# main.net
KiCad netlist of a schematic drawn in Altium Designer
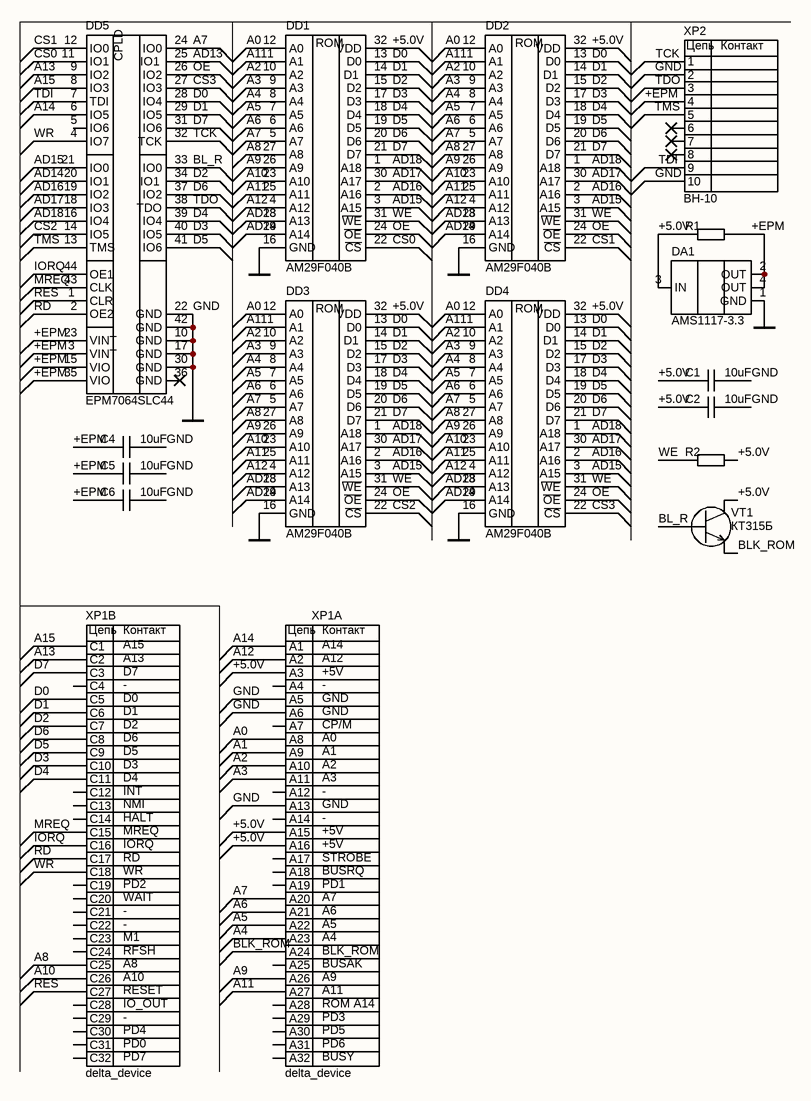
[diagram p0: main.SchDoc]

(export (version "E")
  (design (tool "Eeschema 10.0.6"))
  (components
    (comp (ref "C1") (value "10uF") (footprint "C0805") (libsource (lib "Capacitors") (part "CapCer")))
    (comp (ref "C2") (value "10uF") (footprint "C0805") (libsource (lib "Capacitors") (part "CapCer")))
    (comp (ref "C4") (value "10uF") (footprint "C0805") (libsource (lib "Capacitors") (part "CapCer")))
    (comp (ref "C5") (value "10uF") (footprint "C0805") (libsource (lib "Capacitors") (part "CapCer")))
    (comp (ref "C6") (value "10uF") (footprint "C0805") (libsource (lib "Capacitors") (part "CapCer")))
    (comp (ref "DA1")
      (value "AMS1117-3.3")
      (footprint "SOT229P700X180-4N")
      (libsource (lib "LDO") (part "AMS1117-3.3"))
    )
    (comp (ref "DD1")
      (value "AM29F040B")
      (footprint "DIP254P1524X482-32")
      (libsource (lib "ROM") (part "AM29F040B"))
    )
    (comp (ref "DD2")
      (value "AM29F040B")
      (footprint "DIP254P1524X482-32")
      (libsource (lib "ROM") (part "AM29F040B"))
    )
    (comp (ref "DD3")
      (value "AM29F040B")
      (footprint "DIP254P1524X482-32")
      (libsource (lib "ROM") (part "AM29F040B"))
    )
    (comp (ref "DD4")
      (value "AM29F040B")
      (footprint "DIP254P1524X482-32")
      (libsource (lib "ROM") (part "AM29F040B"))
    )
    (comp (ref "DD5")
      (value "EPM7064SLC44")
      (footprint "PLCC-44-R")
      (description "44-Pin PLCC44")
      (libsource (lib "cpld") (part "EPM7064SLC44"))
    )
    (comp (ref "R1") (value "0 Ом") (footprint "R0603") (libsource (lib "Resistors") (part "Res")))
    (comp (ref "R2") (value "1 кОм") (footprint "R0603") (libsource (lib "Resistors") (part "Res")))
    (comp (ref "VT1")
      (value "КТ315Б")
      (footprint "KT-13")
      (description "NPN Transistor")
      (libsource (lib "Transistors") (part "КТ315Б"))
    )
    (comp (ref "XP1")
      (value "delta_device")
      (footprint "delta-device")
      (libsource (lib "Connectors") (part "delta_device"))
    )
    (comp (ref "XP2")
      (value "BH-10")
      (footprint "BH-10")
      (description "10 Position Total Dual Row 2.54 mm Pitch Straight Male Shrouded Box Header")
      (fields (field (name "MF") "Sullins Connector") (field (name "MP") "SBH11-PBPC-D05-ST-BK"))
      (libsource (lib "Connectors") (part "BH-10"))
    )
  )
  (nets
    (net (code "1") (name "/+5.0V") (class "Default")
      (node (ref "C1") (pin "1") (pinfunction "1_1") (pintype "passive"))
      (node (ref "C2") (pin "1") (pinfunction "1_1") (pintype "passive"))
      (node (ref "DA1") (pin "3") (pinfunction "IN_3") (pintype "passive"))
      (node (ref "DD1") (pin "32") (pinfunction "VDD_32") (pintype "passive"))
      (node (ref "DD2") (pin "32") (pinfunction "VDD_32") (pintype "passive"))
      (node (ref "DD3") (pin "32") (pinfunction "VDD_32") (pintype "passive"))
      (node (ref "DD4") (pin "32") (pinfunction "VDD_32") (pintype "passive"))
      (node (ref "R1") (pin "1") (pinfunction "1_1") (pintype "passive"))
      (node (ref "R2") (pin "2") (pinfunction "2_2") (pintype "passive"))
      (node (ref "VT1") (pin "2") (pinfunction "C_2") (pintype "power_in"))
      (node (ref "XP1") (pin "A15") (pinfunction "A15_A15") (pintype "passive"))
      (node (ref "XP1") (pin "A16") (pinfunction "A16_A16") (pintype "passive"))
      (node (ref "XP1") (pin "A3") (pinfunction "A3_A3") (pintype "passive"))
    )
    (net (code "2") (name "/+EPM") (class "Default")
      (node (ref "C4") (pin "1") (pinfunction "1_1") (pintype "passive"))
      (node (ref "C5") (pin "1") (pinfunction "1_1") (pintype "passive"))
      (node (ref "C6") (pin "1") (pinfunction "1_1") (pintype "passive"))
      (node (ref "DA1") (pin "2") (pinfunction "OUT_2") (pintype "passive"))
      (node (ref "DA1") (pin "4") (pinfunction "OUT_4") (pintype "passive"))
      (node (ref "DD5") (pin "15") (pinfunction "VIO_15") (pintype "passive"))
      (node (ref "DD5") (pin "23") (pinfunction "VINT_23") (pintype "passive"))
      (node (ref "DD5") (pin "3") (pinfunction "VINT_3") (pintype "passive"))
      (node (ref "DD5") (pin "35") (pinfunction "VIO_35") (pintype "passive"))
      (node (ref "R1") (pin "2") (pinfunction "2_2") (pintype "passive"))
      (node (ref "XP2") (pin "4") (pinfunction "4_4") (pintype "passive"))
    )
    (net (code "3") (name "/A0") (class "Default")
      (node (ref "DD1") (pin "12") (pinfunction "A0_12") (pintype "passive"))
      (node (ref "DD2") (pin "12") (pinfunction "A0_12") (pintype "passive"))
      (node (ref "DD3") (pin "12") (pinfunction "A0_12") (pintype "passive"))
      (node (ref "DD4") (pin "12") (pinfunction "A0_12") (pintype "passive"))
      (node (ref "XP1") (pin "A8") (pinfunction "A8_A8") (pintype "passive"))
    )
    (net (code "4") (name "/A1") (class "Default")
      (node (ref "DD1") (pin "11") (pinfunction "A1_11") (pintype "passive"))
      (node (ref "DD2") (pin "11") (pinfunction "A1_11") (pintype "passive"))
      (node (ref "DD3") (pin "11") (pinfunction "A1_11") (pintype "passive"))
      (node (ref "DD4") (pin "11") (pinfunction "A1_11") (pintype "passive"))
      (node (ref "XP1") (pin "A9") (pinfunction "A9_A9") (pintype "passive"))
    )
    (net (code "5") (name "/A2") (class "Default")
      (node (ref "DD1") (pin "10") (pinfunction "A2_10") (pintype "passive"))
      (node (ref "DD2") (pin "10") (pinfunction "A2_10") (pintype "passive"))
      (node (ref "DD3") (pin "10") (pinfunction "A2_10") (pintype "passive"))
      (node (ref "DD4") (pin "10") (pinfunction "A2_10") (pintype "passive"))
      (node (ref "XP1") (pin "A10") (pinfunction "A10_A10") (pintype "passive"))
    )
    (net (code "6") (name "/A3") (class "Default")
      (node (ref "DD1") (pin "9") (pinfunction "A3_9") (pintype "passive"))
      (node (ref "DD2") (pin "9") (pinfunction "A3_9") (pintype "passive"))
      (node (ref "DD3") (pin "9") (pinfunction "A3_9") (pintype "passive"))
      (node (ref "DD4") (pin "9") (pinfunction "A3_9") (pintype "passive"))
      (node (ref "XP1") (pin "A11") (pinfunction "A11_A11") (pintype "passive"))
    )
    (net (code "7") (name "/A4") (class "Default")
      (node (ref "DD1") (pin "8") (pinfunction "A4_8") (pintype "passive"))
      (node (ref "DD2") (pin "8") (pinfunction "A4_8") (pintype "passive"))
      (node (ref "DD3") (pin "8") (pinfunction "A4_8") (pintype "passive"))
      (node (ref "DD4") (pin "8") (pinfunction "A4_8") (pintype "passive"))
      (node (ref "XP1") (pin "A23") (pinfunction "A23_A23") (pintype "passive"))
    )
    (net (code "8") (name "/A5") (class "Default")
      (node (ref "DD1") (pin "7") (pinfunction "A5_7") (pintype "passive"))
      (node (ref "DD2") (pin "7") (pinfunction "A5_7") (pintype "passive"))
      (node (ref "DD3") (pin "7") (pinfunction "A5_7") (pintype "passive"))
      (node (ref "DD4") (pin "7") (pinfunction "A5_7") (pintype "passive"))
      (node (ref "XP1") (pin "A22") (pinfunction "A22_A22") (pintype "passive"))
    )
    (net (code "9") (name "/A6") (class "Default")
      (node (ref "DD1") (pin "6") (pinfunction "A6_6") (pintype "passive"))
      (node (ref "DD2") (pin "6") (pinfunction "A6_6") (pintype "passive"))
      (node (ref "DD3") (pin "6") (pinfunction "A6_6") (pintype "passive"))
      (node (ref "DD4") (pin "6") (pinfunction "A6_6") (pintype "passive"))
      (node (ref "XP1") (pin "A21") (pinfunction "A21_A21") (pintype "passive"))
    )
    (net (code "10") (name "/A7") (class "Default")
      (node (ref "DD1") (pin "5") (pinfunction "A7_5") (pintype "passive"))
      (node (ref "DD2") (pin "5") (pinfunction "A7_5") (pintype "passive"))
      (node (ref "DD3") (pin "5") (pinfunction "A7_5") (pintype "passive"))
      (node (ref "DD4") (pin "5") (pinfunction "A7_5") (pintype "passive"))
      (node (ref "DD5") (pin "24") (pinfunction "IO0_24") (pintype "passive"))
      (node (ref "XP1") (pin "A20") (pinfunction "A20_A20") (pintype "passive"))
    )
    (net (code "11") (name "/A8") (class "Default")
      (node (ref "DD1") (pin "27") (pinfunction "A8_27") (pintype "passive"))
      (node (ref "DD2") (pin "27") (pinfunction "A8_27") (pintype "passive"))
      (node (ref "DD3") (pin "27") (pinfunction "A8_27") (pintype "passive"))
      (node (ref "DD4") (pin "27") (pinfunction "A8_27") (pintype "passive"))
      (node (ref "XP1") (pin "C25") (pinfunction "C25_C25") (pintype "passive"))
    )
    (net (code "12") (name "/A9") (class "Default")
      (node (ref "DD1") (pin "26") (pinfunction "A9_26") (pintype "passive"))
      (node (ref "DD2") (pin "26") (pinfunction "A9_26") (pintype "passive"))
      (node (ref "DD3") (pin "26") (pinfunction "A9_26") (pintype "passive"))
      (node (ref "DD4") (pin "26") (pinfunction "A9_26") (pintype "passive"))
      (node (ref "XP1") (pin "A26") (pinfunction "A26_A26") (pintype "passive"))
    )
    (net (code "13") (name "/A10") (class "Default")
      (node (ref "DD1") (pin "23") (pinfunction "A10_23") (pintype "passive"))
      (node (ref "DD2") (pin "23") (pinfunction "A10_23") (pintype "passive"))
      (node (ref "DD3") (pin "23") (pinfunction "A10_23") (pintype "passive"))
      (node (ref "DD4") (pin "23") (pinfunction "A10_23") (pintype "passive"))
      (node (ref "XP1") (pin "C26") (pinfunction "C26_C26") (pintype "passive"))
    )
    (net (code "14") (name "/A11") (class "Default")
      (node (ref "DD1") (pin "25") (pinfunction "A11_25") (pintype "passive"))
      (node (ref "DD2") (pin "25") (pinfunction "A11_25") (pintype "passive"))
      (node (ref "DD3") (pin "25") (pinfunction "A11_25") (pintype "passive"))
      (node (ref "DD4") (pin "25") (pinfunction "A11_25") (pintype "passive"))
      (node (ref "XP1") (pin "A27") (pinfunction "A27_A27") (pintype "passive"))
    )
    (net (code "15") (name "/A12") (class "Default")
      (node (ref "DD1") (pin "4") (pinfunction "A12_4") (pintype "passive"))
      (node (ref "DD2") (pin "4") (pinfunction "A12_4") (pintype "passive"))
      (node (ref "DD3") (pin "4") (pinfunction "A12_4") (pintype "passive"))
      (node (ref "DD4") (pin "4") (pinfunction "A12_4") (pintype "passive"))
      (node (ref "XP1") (pin "A2") (pinfunction "A2_A2") (pintype "passive"))
    )
    (net (code "16") (name "/A13") (class "Default")
      (node (ref "DD5") (pin "9") (pinfunction "IO2_9") (pintype "passive"))
      (node (ref "XP1") (pin "C2") (pinfunction "C2_C2") (pintype "passive"))
    )
    (net (code "17") (name "/A14") (class "Default")
      (node (ref "DD5") (pin "6") (pinfunction "IO5_6") (pintype "passive"))
      (node (ref "XP1") (pin "A1") (pinfunction "A1_A1") (pintype "passive"))
    )
    (net (code "18") (name "/A15") (class "Default")
      (node (ref "DD5") (pin "8") (pinfunction "IO3_8") (pintype "passive"))
      (node (ref "XP1") (pin "C1") (pinfunction "C1_C1") (pintype "passive"))
    )
    (net (code "19") (name "/AD13") (class "Default")
      (node (ref "DD1") (pin "28") (pinfunction "A13_28") (pintype "passive"))
      (node (ref "DD2") (pin "28") (pinfunction "A13_28") (pintype "passive"))
      (node (ref "DD3") (pin "28") (pinfunction "A13_28") (pintype "passive"))
      (node (ref "DD4") (pin "28") (pinfunction "A13_28") (pintype "passive"))
      (node (ref "DD5") (pin "25") (pinfunction "IO1_25") (pintype "passive"))
    )
    (net (code "20") (name "/AD14") (class "Default")
      (node (ref "DD1") (pin "29") (pinfunction "A14_29") (pintype "passive"))
      (node (ref "DD2") (pin "29") (pinfunction "A14_29") (pintype "passive"))
      (node (ref "DD3") (pin "29") (pinfunction "A14_29") (pintype "passive"))
      (node (ref "DD4") (pin "29") (pinfunction "A14_29") (pintype "passive"))
      (node (ref "DD5") (pin "20") (pinfunction "IO1_20") (pintype "passive"))
    )
    (net (code "21") (name "/AD15") (class "Default")
      (node (ref "DD1") (pin "3") (pinfunction "A15_3") (pintype "passive"))
      (node (ref "DD2") (pin "3") (pinfunction "A15_3") (pintype "passive"))
      (node (ref "DD3") (pin "3") (pinfunction "A15_3") (pintype "passive"))
      (node (ref "DD4") (pin "3") (pinfunction "A15_3") (pintype "passive"))
      (node (ref "DD5") (pin "21") (pinfunction "IO0_21") (pintype "passive"))
    )
    (net (code "22") (name "/AD16") (class "Default")
      (node (ref "DD1") (pin "2") (pinfunction "A16_2") (pintype "passive"))
      (node (ref "DD2") (pin "2") (pinfunction "A16_2") (pintype "passive"))
      (node (ref "DD3") (pin "2") (pinfunction "A16_2") (pintype "passive"))
      (node (ref "DD4") (pin "2") (pinfunction "A16_2") (pintype "passive"))
      (node (ref "DD5") (pin "19") (pinfunction "IO2_19") (pintype "passive"))
    )
    (net (code "23") (name "/AD17") (class "Default")
      (node (ref "DD1") (pin "30") (pinfunction "A17_30") (pintype "passive"))
      (node (ref "DD2") (pin "30") (pinfunction "A17_30") (pintype "passive"))
      (node (ref "DD3") (pin "30") (pinfunction "A17_30") (pintype "passive"))
      (node (ref "DD4") (pin "30") (pinfunction "A17_30") (pintype "passive"))
      (node (ref "DD5") (pin "18") (pinfunction "IO3_18") (pintype "passive"))
    )
    (net (code "24") (name "/AD18") (class "Default")
      (node (ref "DD1") (pin "1") (pinfunction "A18_1") (pintype "passive"))
      (node (ref "DD2") (pin "1") (pinfunction "A18_1") (pintype "passive"))
      (node (ref "DD3") (pin "1") (pinfunction "A18_1") (pintype "passive"))
      (node (ref "DD4") (pin "1") (pinfunction "A18_1") (pintype "passive"))
      (node (ref "DD5") (pin "16") (pinfunction "IO4_16") (pintype "passive"))
    )
    (net (code "25") (name "/BLK_ROM") (class "Default")
      (node (ref "VT1") (pin "1") (pinfunction "E_1") (pintype "power_in"))
      (node (ref "XP1") (pin "A24") (pinfunction "A24_A24") (pintype "passive"))
    )
    (net (code "26") (name "/BL_R") (class "Default")
      (node (ref "DD5") (pin "33") (pinfunction "IO0_33") (pintype "passive"))
      (node (ref "VT1") (pin "3") (pinfunction "B_3") (pintype "power_in"))
    )
    (net (code "27") (name "/CS0") (class "Default")
      (node (ref "DD1") (pin "22") (pinfunction "~{CS}_22") (pintype "passive"))
      (node (ref "DD5") (pin "11") (pinfunction "IO1_11") (pintype "passive"))
    )
    (net (code "28") (name "/CS1") (class "Default")
      (node (ref "DD2") (pin "22") (pinfunction "~{CS}_22") (pintype "passive"))
      (node (ref "DD5") (pin "12") (pinfunction "IO0_12") (pintype "passive"))
    )
    (net (code "29") (name "/CS2") (class "Default")
      (node (ref "DD3") (pin "22") (pinfunction "~{CS}_22") (pintype "passive"))
      (node (ref "DD5") (pin "14") (pinfunction "IO5_14") (pintype "passive"))
    )
    (net (code "30") (name "/CS3") (class "Default")
      (node (ref "DD4") (pin "22") (pinfunction "~{CS}_22") (pintype "passive"))
      (node (ref "DD5") (pin "27") (pinfunction "IO3_27") (pintype "passive"))
    )
    (net (code "31") (name "/D0") (class "Default")
      (node (ref "DD1") (pin "13") (pinfunction "D0_13") (pintype "passive"))
      (node (ref "DD2") (pin "13") (pinfunction "D0_13") (pintype "passive"))
      (node (ref "DD3") (pin "13") (pinfunction "D0_13") (pintype "passive"))
      (node (ref "DD4") (pin "13") (pinfunction "D0_13") (pintype "passive"))
      (node (ref "DD5") (pin "28") (pinfunction "IO4_28") (pintype "passive"))
      (node (ref "XP1") (pin "C5") (pinfunction "C5_C5") (pintype "passive"))
    )
    (net (code "32") (name "/D1") (class "Default")
      (node (ref "DD1") (pin "14") (pinfunction "D1_14") (pintype "passive"))
      (node (ref "DD2") (pin "14") (pinfunction "D1_14") (pintype "passive"))
      (node (ref "DD3") (pin "14") (pinfunction "D1_14") (pintype "passive"))
      (node (ref "DD4") (pin "14") (pinfunction "D1_14") (pintype "passive"))
      (node (ref "DD5") (pin "29") (pinfunction "IO5_29") (pintype "passive"))
      (node (ref "XP1") (pin "C6") (pinfunction "C6_C6") (pintype "passive"))
    )
    (net (code "33") (name "/D2") (class "Default")
      (node (ref "DD1") (pin "15") (pinfunction "D2_15") (pintype "passive"))
      (node (ref "DD2") (pin "15") (pinfunction "D2_15") (pintype "passive"))
      (node (ref "DD3") (pin "15") (pinfunction "D2_15") (pintype "passive"))
      (node (ref "DD4") (pin "15") (pinfunction "D2_15") (pintype "passive"))
      (node (ref "DD5") (pin "34") (pinfunction "IO1_34") (pintype "passive"))
      (node (ref "XP1") (pin "C7") (pinfunction "C7_C7") (pintype "passive"))
    )
    (net (code "34") (name "/D3") (class "Default")
      (node (ref "DD1") (pin "17") (pinfunction "D3_17") (pintype "passive"))
      (node (ref "DD2") (pin "17") (pinfunction "D3_17") (pintype "passive"))
      (node (ref "DD3") (pin "17") (pinfunction "D3_17") (pintype "passive"))
      (node (ref "DD4") (pin "17") (pinfunction "D3_17") (pintype "passive"))
      (node (ref "DD5") (pin "40") (pinfunction "IO5_40") (pintype "passive"))
      (node (ref "XP1") (pin "C10") (pinfunction "C10_C10") (pintype "passive"))
    )
    (net (code "35") (name "/D4") (class "Default")
      (node (ref "DD1") (pin "18") (pinfunction "D4_18") (pintype "passive"))
      (node (ref "DD2") (pin "18") (pinfunction "D4_18") (pintype "passive"))
      (node (ref "DD3") (pin "18") (pinfunction "D4_18") (pintype "passive"))
      (node (ref "DD4") (pin "18") (pinfunction "D4_18") (pintype "passive"))
      (node (ref "DD5") (pin "39") (pinfunction "IO4_39") (pintype "passive"))
      (node (ref "XP1") (pin "C11") (pinfunction "C11_C11") (pintype "passive"))
    )
    (net (code "36") (name "/D5") (class "Default")
      (node (ref "DD1") (pin "19") (pinfunction "D5_19") (pintype "passive"))
      (node (ref "DD2") (pin "19") (pinfunction "D5_19") (pintype "passive"))
      (node (ref "DD3") (pin "19") (pinfunction "D5_19") (pintype "passive"))
      (node (ref "DD4") (pin "19") (pinfunction "D5_19") (pintype "passive"))
      (node (ref "DD5") (pin "41") (pinfunction "IO6_41") (pintype "passive"))
      (node (ref "XP1") (pin "C9") (pinfunction "C9_C9") (pintype "passive"))
    )
    (net (code "37") (name "/D6") (class "Default")
      (node (ref "DD1") (pin "20") (pinfunction "D6_20") (pintype "passive"))
      (node (ref "DD2") (pin "20") (pinfunction "D6_20") (pintype "passive"))
      (node (ref "DD3") (pin "20") (pinfunction "D6_20") (pintype "passive"))
      (node (ref "DD4") (pin "20") (pinfunction "D6_20") (pintype "passive"))
      (node (ref "DD5") (pin "37") (pinfunction "IO2_37") (pintype "passive"))
      (node (ref "XP1") (pin "C8") (pinfunction "C8_C8") (pintype "passive"))
    )
    (net (code "38") (name "/D7") (class "Default")
      (node (ref "DD1") (pin "21") (pinfunction "D7_21") (pintype "passive"))
      (node (ref "DD2") (pin "21") (pinfunction "D7_21") (pintype "passive"))
      (node (ref "DD3") (pin "21") (pinfunction "D7_21") (pintype "passive"))
      (node (ref "DD4") (pin "21") (pinfunction "D7_21") (pintype "passive"))
      (node (ref "DD5") (pin "31") (pinfunction "IO6_31") (pintype "passive"))
      (node (ref "XP1") (pin "C3") (pinfunction "C3_C3") (pintype "passive"))
    )
    (net (code "39") (name "/IORQ") (class "Default")
      (node (ref "DD5") (pin "44") (pinfunction "OE1_44") (pintype "passive"))
      (node (ref "XP1") (pin "C16") (pinfunction "C16_C16") (pintype "passive"))
    )
    (net (code "40") (name "/MREQ") (class "Default")
      (node (ref "DD5") (pin "43") (pinfunction "CLK_43") (pintype "passive"))
      (node (ref "XP1") (pin "C15") (pinfunction "C15_C15") (pintype "passive"))
    )
    (net (code "41") (name "/OE") (class "Default")
      (node (ref "DD1") (pin "24") (pinfunction "~{OE}_24") (pintype "passive"))
      (node (ref "DD2") (pin "24") (pinfunction "~{OE}_24") (pintype "passive"))
      (node (ref "DD3") (pin "24") (pinfunction "~{OE}_24") (pintype "passive"))
      (node (ref "DD4") (pin "24") (pinfunction "~{OE}_24") (pintype "passive"))
      (node (ref "DD5") (pin "26") (pinfunction "IO2_26") (pintype "passive"))
    )
    (net (code "42") (name "/RD") (class "Default")
      (node (ref "DD5") (pin "2") (pinfunction "OE2_2") (pintype "passive"))
      (node (ref "XP1") (pin "C17") (pinfunction "C17_C17") (pintype "passive"))
    )
    (net (code "43") (name "/RES") (class "Default")
      (node (ref "DD5") (pin "1") (pinfunction "CLR_1") (pintype "passive"))
      (node (ref "XP1") (pin "C27") (pinfunction "C27_C27") (pintype "passive"))
    )
    (net (code "44") (name "/TCK") (class "Default")
      (node (ref "DD5") (pin "32") (pinfunction "TCK_32") (pintype "passive"))
      (node (ref "XP2") (pin "1") (pinfunction "1_1") (pintype "passive"))
    )
    (net (code "45") (name "/TDI") (class "Default")
      (node (ref "DD5") (pin "7") (pinfunction "TDI_7") (pintype "passive"))
      (node (ref "XP2") (pin "9") (pinfunction "9_9") (pintype "passive"))
    )
    (net (code "46") (name "/TDO") (class "Default")
      (node (ref "DD5") (pin "38") (pinfunction "TDO_38") (pintype "passive"))
      (node (ref "XP2") (pin "3") (pinfunction "3_3") (pintype "passive"))
    )
    (net (code "47") (name "/TMS") (class "Default")
      (node (ref "DD5") (pin "13") (pinfunction "TMS_13") (pintype "passive"))
      (node (ref "XP2") (pin "5") (pinfunction "5_5") (pintype "passive"))
    )
    (net (code "48") (name "/WE") (class "Default")
      (node (ref "DD1") (pin "31") (pinfunction "~{WE}_31") (pintype "passive"))
      (node (ref "DD2") (pin "31") (pinfunction "~{WE}_31") (pintype "passive"))
      (node (ref "DD3") (pin "31") (pinfunction "~{WE}_31") (pintype "passive"))
      (node (ref "DD4") (pin "31") (pinfunction "~{WE}_31") (pintype "passive"))
      (node (ref "R2") (pin "1") (pinfunction "1_1") (pintype "passive"))
    )
    (net (code "49") (name "/WR") (class "Default")
      (node (ref "DD5") (pin "4") (pinfunction "IO7_4") (pintype "passive"))
      (node (ref "XP1") (pin "C18") (pinfunction "C18_C18") (pintype "passive"))
    )
    (net (code "50") (name "GND") (class "Default")
      (node (ref "C1") (pin "2") (pinfunction "2_2") (pintype "passive"))
      (node (ref "C2") (pin "2") (pinfunction "2_2") (pintype "passive"))
      (node (ref "C4") (pin "2") (pinfunction "2_2") (pintype "passive"))
      (node (ref "C5") (pin "2") (pinfunction "2_2") (pintype "passive"))
      (node (ref "C6") (pin "2") (pinfunction "2_2") (pintype "passive"))
      (node (ref "DA1") (pin "1") (pinfunction "GND_1") (pintype "passive"))
      (node (ref "DD1") (pin "16") (pinfunction "GND_16") (pintype "passive"))
      (node (ref "DD2") (pin "16") (pinfunction "GND_16") (pintype "passive"))
      (node (ref "DD3") (pin "16") (pinfunction "GND_16") (pintype "passive"))
      (node (ref "DD4") (pin "16") (pinfunction "GND_16") (pintype "passive"))
      (node (ref "DD5") (pin "10") (pinfunction "GND_10") (pintype "passive"))
      (node (ref "DD5") (pin "17") (pinfunction "GND_17") (pintype "passive"))
      (node (ref "DD5") (pin "22") (pinfunction "GND_22") (pintype "passive"))
      (node (ref "DD5") (pin "30") (pinfunction "GND_30") (pintype "passive"))
      (node (ref "DD5") (pin "42") (pinfunction "GND_42") (pintype "passive"))
      (node (ref "XP1") (pin "A13") (pinfunction "A13_A13") (pintype "passive"))
      (node (ref "XP1") (pin "A5") (pinfunction "A5_A5") (pintype "passive"))
      (node (ref "XP1") (pin "A6") (pinfunction "A6_A6") (pintype "passive"))
      (node (ref "XP2") (pin "10") (pinfunction "10_10") (pintype "passive"))
      (node (ref "XP2") (pin "2") (pinfunction "2_2") (pintype "passive"))
    )
    (net (code "51") (name "unconnected-(DD5-GND-Pad36)") (class "Default")
      (node (ref "DD5") (pin "36") (pinfunction "GND_36") (pintype "passive+no_connect"))
    )
    (net (code "52") (name "unconnected-(DD5-IO6-Pad5)") (class "Default")
      (node (ref "DD5") (pin "5") (pinfunction "IO6_5") (pintype "passive"))
    )
    (net (code "53") (name "unconnected-(XP1-PadA4)") (class "Default")
      (node (ref "XP1") (pin "A4") (pinfunction "A4_A4") (pintype "passive"))
    )
    (net (code "54") (name "unconnected-(XP1-PadA7)") (class "Default")
      (node (ref "XP1") (pin "A7") (pinfunction "A7_A7") (pintype "passive"))
    )
    (net (code "55") (name "unconnected-(XP1-PadA12)") (class "Default")
      (node (ref "XP1") (pin "A12") (pinfunction "A12_A12") (pintype "passive"))
    )
    (net (code "56") (name "unconnected-(XP1-PadA14)") (class "Default")
      (node (ref "XP1") (pin "A14") (pinfunction "A14_A14") (pintype "passive"))
    )
    (net (code "57") (name "unconnected-(XP1-PadA17)") (class "Default")
      (node (ref "XP1") (pin "A17") (pinfunction "A17_A17") (pintype "passive"))
    )
    (net (code "58") (name "unconnected-(XP1-PadA18)") (class "Default")
      (node (ref "XP1") (pin "A18") (pinfunction "A18_A18") (pintype "passive"))
    )
    (net (code "59") (name "unconnected-(XP1-PadA19)") (class "Default")
      (node (ref "XP1") (pin "A19") (pinfunction "A19_A19") (pintype "passive"))
    )
    (net (code "60") (name "unconnected-(XP1-PadA25)") (class "Default")
      (node (ref "XP1") (pin "A25") (pinfunction "A25_A25") (pintype "passive"))
    )
    (net (code "61") (name "unconnected-(XP1-PadA28)") (class "Default")
      (node (ref "XP1") (pin "A28") (pinfunction "A28_A28") (pintype "passive"))
    )
    (net (code "62") (name "unconnected-(XP1-PadA29)") (class "Default")
      (node (ref "XP1") (pin "A29") (pinfunction "A29_A29") (pintype "passive"))
    )
    (net (code "63") (name "unconnected-(XP1-PadA30)") (class "Default")
      (node (ref "XP1") (pin "A30") (pinfunction "A30_A30") (pintype "passive"))
    )
    (net (code "64") (name "unconnected-(XP1-PadA31)") (class "Default")
      (node (ref "XP1") (pin "A31") (pinfunction "A31_A31") (pintype "passive"))
    )
    (net (code "65") (name "unconnected-(XP1-PadA32)") (class "Default")
      (node (ref "XP1") (pin "A32") (pinfunction "A32_A32") (pintype "passive"))
    )
    (net (code "66") (name "unconnected-(XP1-PadC4)") (class "Default")
      (node (ref "XP1") (pin "C4") (pinfunction "C4_C4") (pintype "passive"))
    )
    (net (code "67") (name "unconnected-(XP1-PadC12)") (class "Default")
      (node (ref "XP1") (pin "C12") (pinfunction "C12_C12") (pintype "passive"))
    )
    (net (code "68") (name "unconnected-(XP1-PadC13)") (class "Default")
      (node (ref "XP1") (pin "C13") (pinfunction "C13_C13") (pintype "passive"))
    )
    (net (code "69") (name "unconnected-(XP1-PadC14)") (class "Default")
      (node (ref "XP1") (pin "C14") (pinfunction "C14_C14") (pintype "passive"))
    )
    (net (code "70") (name "unconnected-(XP1-PadC19)") (class "Default")
      (node (ref "XP1") (pin "C19") (pinfunction "C19_C19") (pintype "passive"))
    )
    (net (code "71") (name "unconnected-(XP1-PadC20)") (class "Default")
      (node (ref "XP1") (pin "C20") (pinfunction "C20_C20") (pintype "passive"))
    )
    (net (code "72") (name "unconnected-(XP1-PadC21)") (class "Default")
      (node (ref "XP1") (pin "C21") (pinfunction "C21_C21") (pintype "passive"))
    )
    (net (code "73") (name "unconnected-(XP1-PadC22)") (class "Default")
      (node (ref "XP1") (pin "C22") (pinfunction "C22_C22") (pintype "passive"))
    )
    (net (code "74") (name "unconnected-(XP1-PadC23)") (class "Default")
      (node (ref "XP1") (pin "C23") (pinfunction "C23_C23") (pintype "passive"))
    )
    (net (code "75") (name "unconnected-(XP1-PadC24)") (class "Default")
      (node (ref "XP1") (pin "C24") (pinfunction "C24_C24") (pintype "passive"))
    )
    (net (code "76") (name "unconnected-(XP1-PadC28)") (class "Default")
      (node (ref "XP1") (pin "C28") (pinfunction "C28_C28") (pintype "passive"))
    )
    (net (code "77") (name "unconnected-(XP1-PadC29)") (class "Default")
      (node (ref "XP1") (pin "C29") (pinfunction "C29_C29") (pintype "passive"))
    )
    (net (code "78") (name "unconnected-(XP1-PadC30)") (class "Default")
      (node (ref "XP1") (pin "C30") (pinfunction "C30_C30") (pintype "passive"))
    )
    (net (code "79") (name "unconnected-(XP1-PadC31)") (class "Default")
      (node (ref "XP1") (pin "C31") (pinfunction "C31_C31") (pintype "passive"))
    )
    (net (code "80") (name "unconnected-(XP1-PadC32)") (class "Default")
      (node (ref "XP1") (pin "C32") (pinfunction "C32_C32") (pintype "passive"))
    )
    (net (code "81") (name "unconnected-(XP2-Pad6)") (class "Default")
      (node (ref "XP2") (pin "6") (pinfunction "6_6") (pintype "passive+no_connect"))
    )
    (net (code "82") (name "unconnected-(XP2-Pad7)") (class "Default")
      (node (ref "XP2") (pin "7") (pinfunction "7_7") (pintype "passive+no_connect"))
    )
    (net (code "83") (name "unconnected-(XP2-Pad8)") (class "Default")
      (node (ref "XP2") (pin "8") (pinfunction "8_8") (pintype "passive+no_connect"))
    )
  )
)
